# dev_kit.net
KiCad netlist of a schematic drawn in EasyEDA
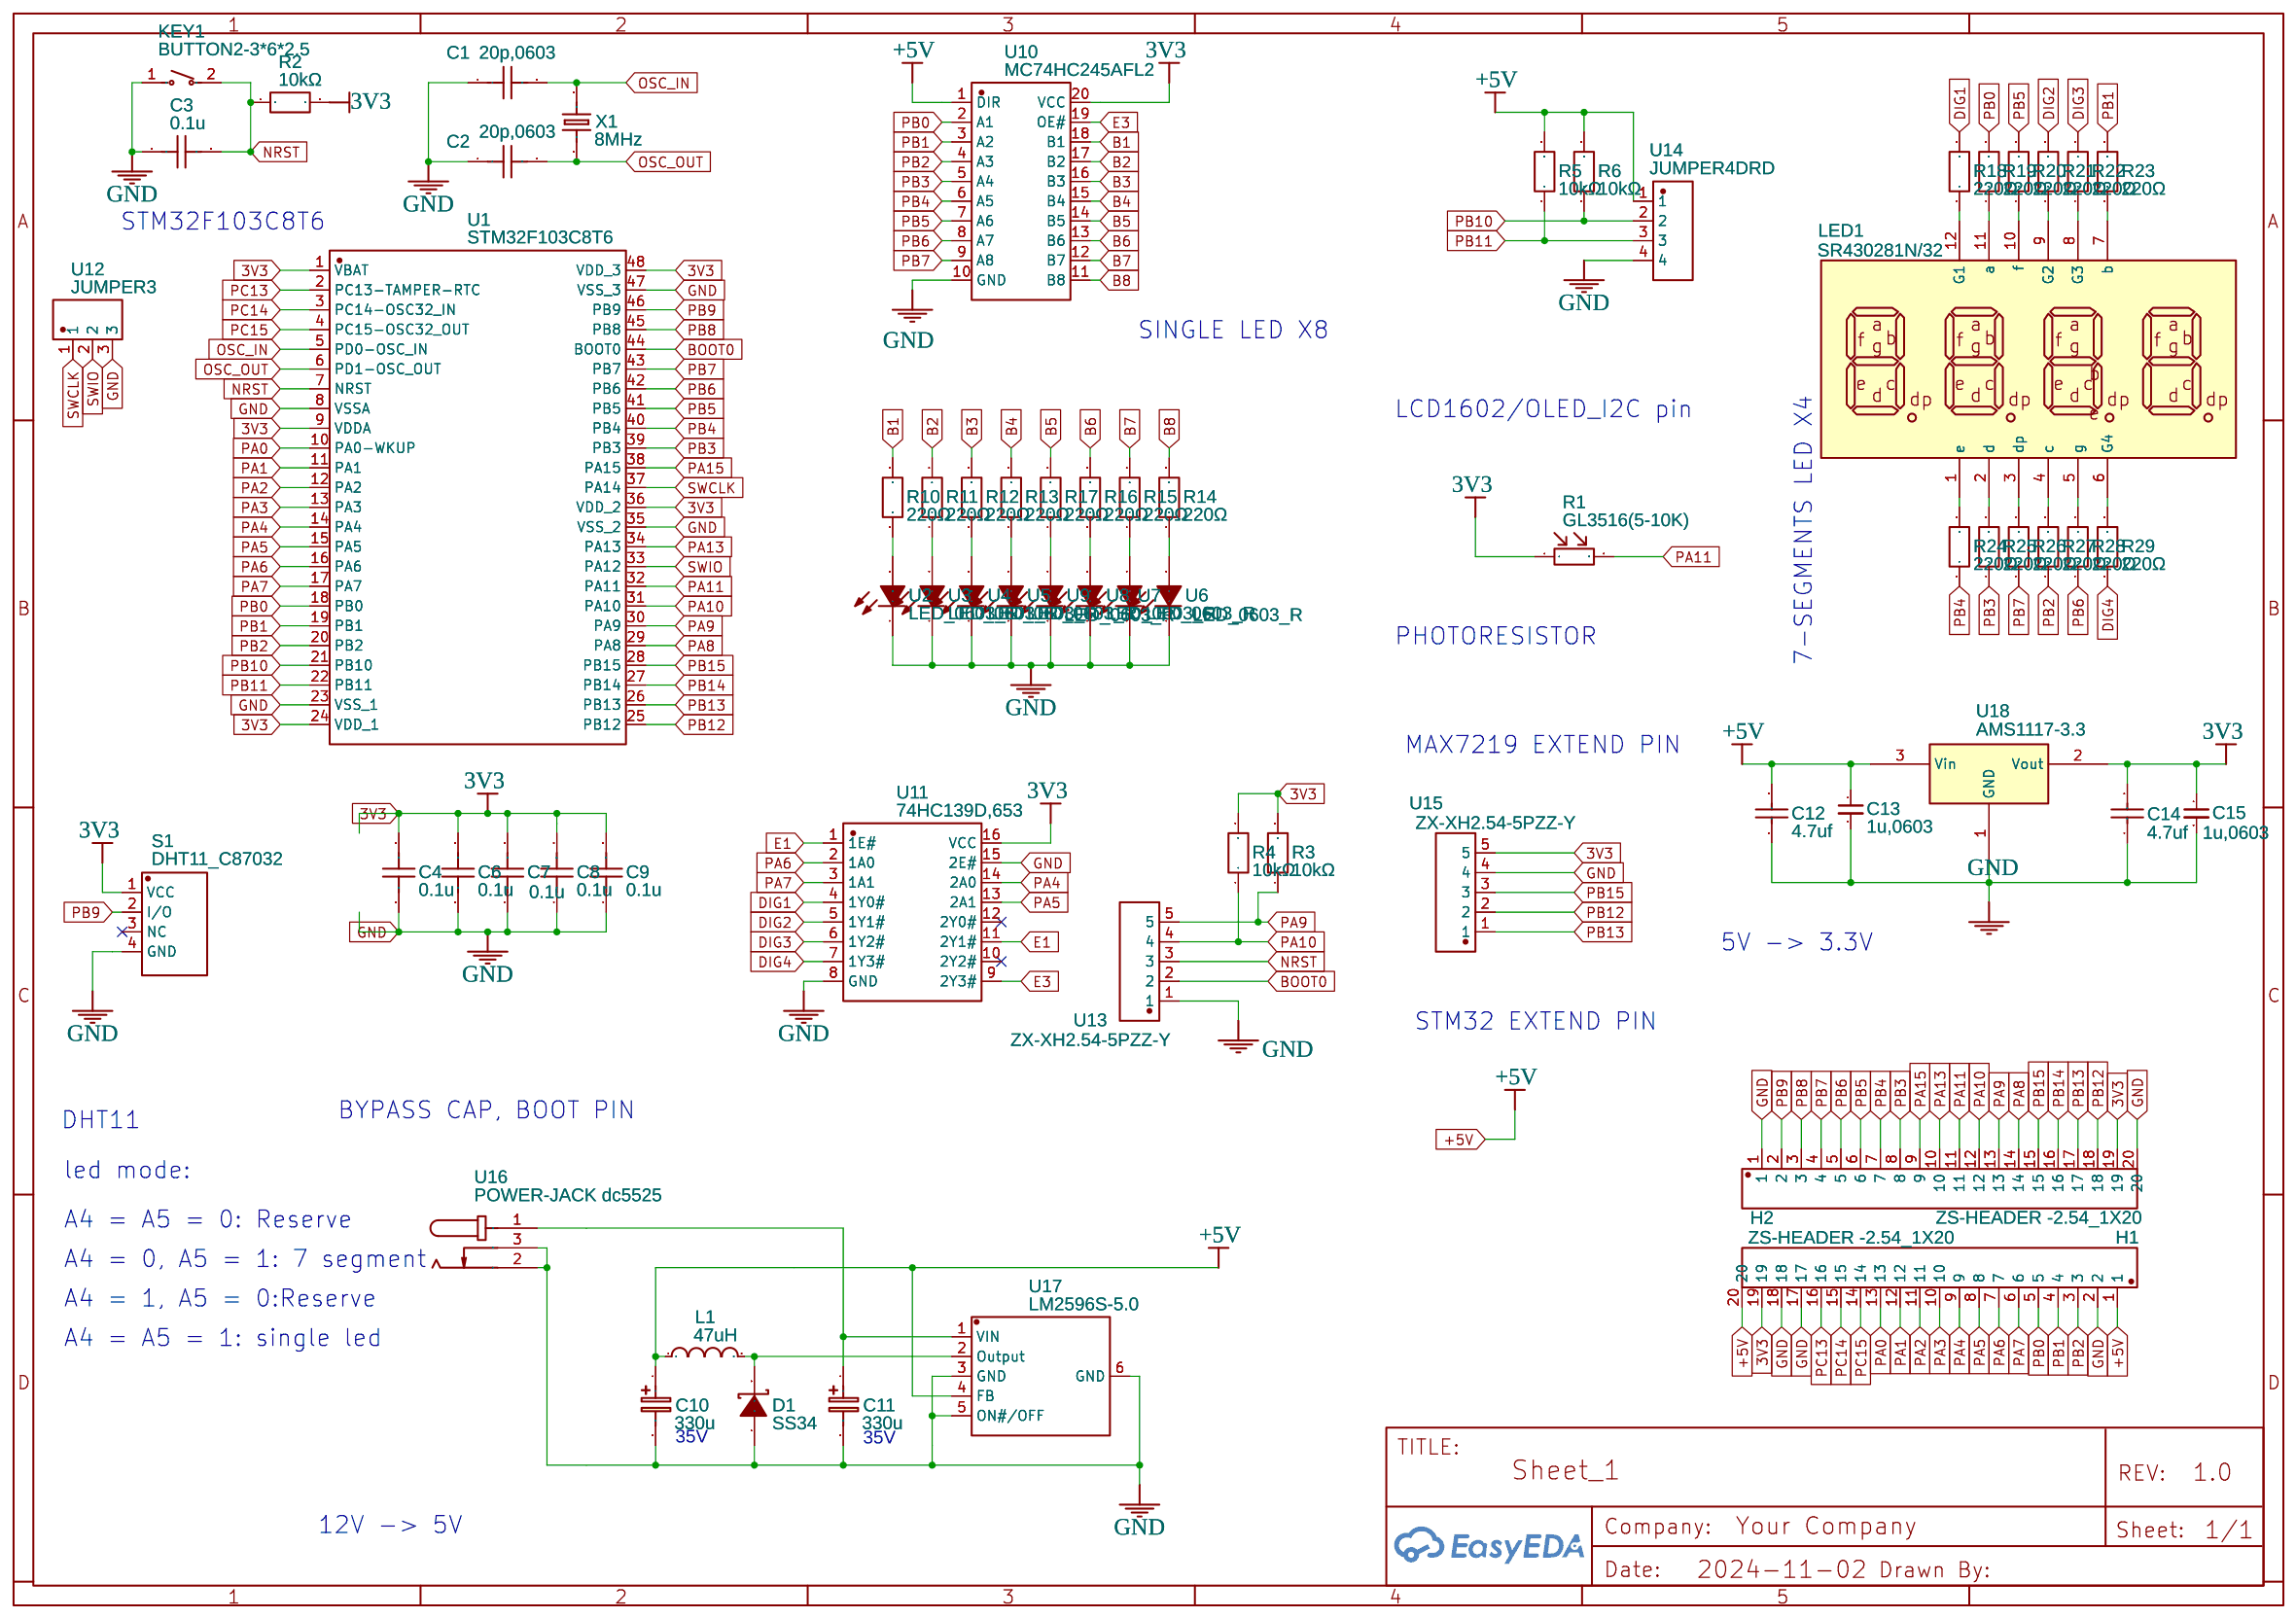
[diagram p0: schematic sheet]

(export (version "E")
  (design (tool "Eeschema 10.0.6"))
  (components
    (comp (ref "C1") (value "20p,0603") (libsource (lib "") (part "C_0603_US_1")))
    (comp (ref "C2") (value "20p,0603") (libsource (lib "") (part "C_0603_US_1")))
    (comp (ref "C3") (value "0.1u") (libsource (lib "") (part "C_0603_US_1")))
    (comp (ref "C4") (value "0.1u") (libsource (lib "") (part "C_0603_US")))
    (comp (ref "C6") (value "0.1u") (libsource (lib "") (part "C_0603_US")))
    (comp (ref "C7") (value "0.1u") (libsource (lib "") (part "C_0603_US")))
    (comp (ref "C8") (value "0.1u") (libsource (lib "") (part "C_0603_US")))
    (comp (ref "C9") (value "0.1u") (libsource (lib "") (part "C_0603_US")))
    (comp (ref "C10")
      (value "330u")
      (fields (field (name "Manufacturer Part") "?"))
      (libsource (lib "") (part "Cap_Electrolytic(SMD)_D8.0XH10.5_EU"))
    )
    (comp (ref "C11")
      (value "330u")
      (fields (field (name "Manufacturer Part") "?"))
      (libsource (lib "") (part "Cap_Electrolytic(SMD)_D8.0XH10.5_EU"))
    )
    (comp (ref "C12")
      (value "4.7uf")
      (fields (field (name "Manufacturer Part") "?"))
      (libsource (lib "") (part "Unknown_890_-400"))
    )
    (comp (ref "C13") (value "1u,0603") (libsource (lib "") (part "C_0603")))
    (comp (ref "C14")
      (value "4.7uf")
      (fields (field (name "Manufacturer Part") "?"))
      (libsource (lib "") (part "Unknown_1070_-400"))
    )
    (comp (ref "C15") (value "1u,0603") (libsource (lib "") (part "C_0603")))
    (comp (ref "D1")
      (value "SS34")
      (fields (field (name "Manufacturer") "Yenji"))
      (libsource (lib "") (part "Unknown_375_-105"))
    )
    (comp (ref "H1") (value "ZS-HEADER -2.54_1X20") (libsource (lib "") (part "ZS-HEADER -2.54_1X20_1")))
    (comp (ref "H2") (value "ZS-HEADER -2.54_1X20") (libsource (lib "") (part "ZS-HEADER -2.54_1X20")))
    (comp (ref "KEY1") (value "BUTTON2-3*6*2.5") (libsource (lib "") (part "BUTTON2-3*6*2.5")))
    (comp (ref "L1")
      (value "47uH")
      (fields (field (name "Manufacturer Part") "CDRH127NP-470MC") (field (name "Manufacturer") "Sumida"))
      (libsource (lib "") (part "CDRH127NP-470MC"))
    )
    (comp (ref "LED1")
      (value "SR430281N/32")
      (fields (field (name "Manufacturer") "ARKLED(方舟)"))
      (libsource (lib "") (part "SR430281N/32"))
    )
    (comp (ref "R1")
      (value "GL3516(5-10K)")
      (fields (field (name "Manufacturer Part") "GL3516（5-10K）") (field (name "Manufacturer") "JCHL(晶创和立)"))
      (libsource (lib "") (part "GL3516(5-10K)"))
    )
    (comp (ref "R2")
      (value "10kΩ")
      (fields (field (name "Manufacturer Part") "TD03E1002BT") (field (name "Manufacturer") "FH(风华)"))
      (libsource (lib "") (part "TD03E1002BT_1"))
    )
    (comp (ref "R3")
      (value "10kΩ")
      (fields (field (name "Manufacturer Part") "TD03E1002BT") (field (name "Manufacturer") "FH(风华)"))
      (libsource (lib "") (part "TD03E1002BT"))
    )
    (comp (ref "R4")
      (value "10kΩ")
      (fields (field (name "Manufacturer Part") "TD03E1002BT") (field (name "Manufacturer") "FH(风华)"))
      (libsource (lib "") (part "TD03E1002BT"))
    )
    (comp (ref "R5")
      (value "10kΩ")
      (fields (field (name "Manufacturer Part") "TD03E1002BT") (field (name "Manufacturer") "FH(风华)"))
      (libsource (lib "") (part "TD03E1002BT"))
    )
    (comp (ref "R6")
      (value "10kΩ")
      (fields (field (name "Manufacturer Part") "TD03E1002BT") (field (name "Manufacturer") "FH(风华)"))
      (libsource (lib "") (part "TD03E1002BT"))
    )
    (comp (ref "R10")
      (value "220Ω")
      (fields
        (field (name "Manufacturer Part") "CRCW0603220RFKEA")
        (field (name "Manufacturer") "VISHAY(威世)")
      )
      (libsource (lib "") (part "CRCW0603220RFKEA"))
    )
    (comp (ref "R11")
      (value "220Ω")
      (fields
        (field (name "Manufacturer Part") "CRCW0603220RFKEA")
        (field (name "Manufacturer") "VISHAY(威世)")
      )
      (libsource (lib "") (part "CRCW0603220RFKEA"))
    )
    (comp (ref "R12")
      (value "220Ω")
      (fields
        (field (name "Manufacturer Part") "CRCW0603220RFKEA")
        (field (name "Manufacturer") "VISHAY(威世)")
      )
      (libsource (lib "") (part "CRCW0603220RFKEA"))
    )
    (comp (ref "R13")
      (value "220Ω")
      (fields
        (field (name "Manufacturer Part") "CRCW0603220RFKEA")
        (field (name "Manufacturer") "VISHAY(威世)")
      )
      (libsource (lib "") (part "CRCW0603220RFKEA"))
    )
    (comp (ref "R14")
      (value "220Ω")
      (fields
        (field (name "Manufacturer Part") "CRCW0603220RFKEA")
        (field (name "Manufacturer") "VISHAY(威世)")
      )
      (libsource (lib "") (part "CRCW0603220RFKEA"))
    )
    (comp (ref "R15")
      (value "220Ω")
      (fields
        (field (name "Manufacturer Part") "CRCW0603220RFKEA")
        (field (name "Manufacturer") "VISHAY(威世)")
      )
      (libsource (lib "") (part "CRCW0603220RFKEA"))
    )
    (comp (ref "R16")
      (value "220Ω")
      (fields
        (field (name "Manufacturer Part") "CRCW0603220RFKEA")
        (field (name "Manufacturer") "VISHAY(威世)")
      )
      (libsource (lib "") (part "CRCW0603220RFKEA"))
    )
    (comp (ref "R17")
      (value "220Ω")
      (fields
        (field (name "Manufacturer Part") "CRCW0603220RFKEA")
        (field (name "Manufacturer") "VISHAY(威世)")
      )
      (libsource (lib "") (part "CRCW0603220RFKEA"))
    )
    (comp (ref "R18")
      (value "220Ω")
      (fields
        (field (name "Manufacturer Part") "CRCW0603220RFKEA")
        (field (name "Manufacturer") "VISHAY(威世)")
      )
      (libsource (lib "") (part "CRCW0603220RFKEA"))
    )
    (comp (ref "R19")
      (value "220Ω")
      (fields
        (field (name "Manufacturer Part") "CRCW0603220RFKEA")
        (field (name "Manufacturer") "VISHAY(威世)")
      )
      (libsource (lib "") (part "CRCW0603220RFKEA"))
    )
    (comp (ref "R20")
      (value "220Ω")
      (fields
        (field (name "Manufacturer Part") "CRCW0603220RFKEA")
        (field (name "Manufacturer") "VISHAY(威世)")
      )
      (libsource (lib "") (part "CRCW0603220RFKEA"))
    )
    (comp (ref "R21")
      (value "220Ω")
      (fields
        (field (name "Manufacturer Part") "CRCW0603220RFKEA")
        (field (name "Manufacturer") "VISHAY(威世)")
      )
      (libsource (lib "") (part "CRCW0603220RFKEA"))
    )
    (comp (ref "R22")
      (value "220Ω")
      (fields
        (field (name "Manufacturer Part") "CRCW0603220RFKEA")
        (field (name "Manufacturer") "VISHAY(威世)")
      )
      (libsource (lib "") (part "CRCW0603220RFKEA"))
    )
    (comp (ref "R23")
      (value "220Ω")
      (fields
        (field (name "Manufacturer Part") "CRCW0603220RFKEA")
        (field (name "Manufacturer") "VISHAY(威世)")
      )
      (libsource (lib "") (part "CRCW0603220RFKEA"))
    )
    (comp (ref "R24")
      (value "220Ω")
      (fields
        (field (name "Manufacturer Part") "CRCW0603220RFKEA")
        (field (name "Manufacturer") "VISHAY(威世)")
      )
      (libsource (lib "") (part "CRCW0603220RFKEA"))
    )
    (comp (ref "R25")
      (value "220Ω")
      (fields
        (field (name "Manufacturer Part") "CRCW0603220RFKEA")
        (field (name "Manufacturer") "VISHAY(威世)")
      )
      (libsource (lib "") (part "CRCW0603220RFKEA"))
    )
    (comp (ref "R26")
      (value "220Ω")
      (fields
        (field (name "Manufacturer Part") "CRCW0603220RFKEA")
        (field (name "Manufacturer") "VISHAY(威世)")
      )
      (libsource (lib "") (part "CRCW0603220RFKEA"))
    )
    (comp (ref "R27")
      (value "220Ω")
      (fields
        (field (name "Manufacturer Part") "CRCW0603220RFKEA")
        (field (name "Manufacturer") "VISHAY(威世)")
      )
      (libsource (lib "") (part "CRCW0603220RFKEA"))
    )
    (comp (ref "R28")
      (value "220Ω")
      (fields
        (field (name "Manufacturer Part") "CRCW0603220RFKEA")
        (field (name "Manufacturer") "VISHAY(威世)")
      )
      (libsource (lib "") (part "CRCW0603220RFKEA"))
    )
    (comp (ref "R29")
      (value "220Ω")
      (fields
        (field (name "Manufacturer Part") "CRCW0603220RFKEA")
        (field (name "Manufacturer") "VISHAY(威世)")
      )
      (libsource (lib "") (part "CRCW0603220RFKEA"))
    )
    (comp (ref "S1")
      (value "DHT11_C87032")
      (fields (field (name "Manufacturer Part") "DHT11") (field (name "Manufacturer") "AOSONG"))
      (libsource (lib "") (part "DHT11_C87032"))
    )
    (comp (ref "U1")
      (value "STM32F103C8T6")
      (fields (field (name "Manufacturer") "ST(意法半导体)"))
      (libsource (lib "") (part "STM32F103C8T6"))
    )
    (comp (ref "U2") (value "LED_0603_R") (libsource (lib "") (part "LED_0603_R")))
    (comp (ref "U3") (value "LED_0603_R") (libsource (lib "") (part "LED_0603_R")))
    (comp (ref "U4") (value "LED_0603_R") (libsource (lib "") (part "LED_0603_R")))
    (comp (ref "U5") (value "LED_0603_R") (libsource (lib "") (part "LED_0603_R")))
    (comp (ref "U6") (value "LED_0603_R") (libsource (lib "") (part "LED_0603_R")))
    (comp (ref "U7") (value "LED_0603_R") (libsource (lib "") (part "LED_0603_R")))
    (comp (ref "U8") (value "LED_0603_R") (libsource (lib "") (part "LED_0603_R")))
    (comp (ref "U9") (value "LED_0603_R") (libsource (lib "") (part "LED_0603_R")))
    (comp (ref "U10")
      (value "MC74HC245AFL2")
      (fields (field (name "Manufacturer") "MOTOROLA(摩托罗拉)"))
      (libsource (lib "") (part "MC74HC245AFL2"))
    )
    (comp (ref "U11")
      (value "74HC139D,653")
      (fields (field (name "Manufacturer") "Nexperia(安世)"))
      (libsource (lib "") (part "74HC139D,653"))
    )
    (comp (ref "U12")
      (value "JUMPER3")
      (fields (field (name "Manufacturer Part") "Jumper3"))
      (libsource (lib "") (part "JUMPER3"))
    )
    (comp (ref "U13")
      (value "ZX-XH2.54-5PZZ-Y")
      (fields (field (name "Manufacturer") "Megastar(兆星)"))
      (libsource (lib "") (part "ZX-XH2.54-5PZZ-Y"))
    )
    (comp (ref "U14")
      (value "JUMPER4DRD")
      (fields (field (name "Manufacturer Part") "Jumper4"))
      (libsource (lib "") (part "JUMPER4DRD"))
    )
    (comp (ref "U15")
      (value "ZX-XH2.54-5PZZ-Y")
      (fields (field (name "Manufacturer") "Megastar(兆星)"))
      (libsource (lib "") (part "ZX-XH2.54-5PZZ-Y"))
    )
    (comp (ref "U16")
      (value "POWER-JACK dc5525")
      (fields (field (name "Manufacturer Part") "POWER-JACK"))
      (libsource (lib "") (part "POWER-JACK dc5525"))
    )
    (comp (ref "U17")
      (value "LM2596S-5.0")
      (fields
        (field (name "Manufacturer Part") "LM2596S-5.0/NOPB")
        (field (name "Manufacturer") "Texas Instruments")
      )
      (libsource (lib "") (part "Unknown_520_-120"))
    )
    (comp (ref "U18")
      (value "AMS1117-3.3")
      (fields (field (name "Manufacturer Part") "?"))
      (libsource (lib "") (part "Unknown_1000_-420"))
    )
    (comp (ref "X1")
      (value "8MHz")
      (fields
        (field (name "Manufacturer Part") "49S-8.00-20-10-10/A")
        (field (name "Manufacturer") "LIMING(利明)")
      )
      (libsource (lib "") (part "49S-8.00-20-10-10/A"))
    )
  )
  (nets
    (net (code "1") (name "+5V") (class "Default")
      (node (ref "C10") (pin "1") (pinfunction "1_1") (pintype "unspecified"))
      (node (ref "C12") (pin "2") (pinfunction "2_2") (pintype "unspecified"))
      (node (ref "C13") (pin "1") (pintype "unspecified"))
      (node (ref "H2") (pin "1") (pinfunction "1_1") (pintype "unspecified"))
      (node (ref "H2") (pin "20") (pinfunction "20_20") (pintype "unspecified"))
      (node (ref "L1") (pin "1") (pinfunction "1_1") (pintype "unspecified"))
      (node (ref "R5") (pin "2") (pinfunction "2_2") (pintype "unspecified"))
      (node (ref "R6") (pin "2") (pinfunction "2_2") (pintype "unspecified"))
      (node (ref "U10") (pin "1") (pinfunction "DIR_1") (pintype "unspecified"))
      (node (ref "U14") (pin "1") (pinfunction "1_1") (pintype "unspecified"))
      (node (ref "U17") (pin "4") (pinfunction "FB_4") (pintype "unspecified"))
      (node (ref "U18") (pin "3") (pinfunction "Vin_3") (pintype "unspecified"))
    )
    (net (code "2") (name "3V3") (class "Default")
      (node (ref "C14") (pin "2") (pinfunction "2_2") (pintype "unspecified"))
      (node (ref "C15") (pin "1") (pintype "unspecified"))
      (node (ref "C4") (pin "2") (pinfunction "2_2") (pintype "unspecified"))
      (node (ref "C6") (pin "2") (pinfunction "2_2") (pintype "unspecified"))
      (node (ref "C7") (pin "2") (pinfunction "2_2") (pintype "unspecified"))
      (node (ref "C8") (pin "2") (pinfunction "2_2") (pintype "unspecified"))
      (node (ref "C9") (pin "2") (pinfunction "2_2") (pintype "unspecified"))
      (node (ref "H1") (pin "19") (pinfunction "19_19") (pintype "unspecified"))
      (node (ref "H2") (pin "19") (pinfunction "19_19") (pintype "unspecified"))
      (node (ref "R1") (pin "1") (pinfunction "1_1") (pintype "input"))
      (node (ref "R2") (pin "2") (pinfunction "2_2") (pintype "unspecified"))
      (node (ref "R3") (pin "2") (pinfunction "2_2") (pintype "unspecified"))
      (node (ref "R4") (pin "2") (pinfunction "2_2") (pintype "unspecified"))
      (node (ref "S1") (pin "1") (pinfunction "VCC_1") (pintype "unspecified"))
      (node (ref "U1") (pin "1") (pinfunction "VBAT_1") (pintype "unspecified"))
      (node (ref "U1") (pin "24") (pinfunction "VDD_1_24") (pintype "unspecified"))
      (node (ref "U1") (pin "36") (pinfunction "VDD_2_36") (pintype "unspecified"))
      (node (ref "U1") (pin "48") (pinfunction "VDD_3_48") (pintype "unspecified"))
      (node (ref "U1") (pin "9") (pinfunction "VDDA_9") (pintype "unspecified"))
      (node (ref "U10") (pin "20") (pinfunction "VCC_20") (pintype "unspecified"))
      (node (ref "U11") (pin "16") (pinfunction "VCC_16") (pintype "unspecified"))
      (node (ref "U15") (pin "5") (pinfunction "5_5") (pintype "unspecified"))
      (node (ref "U18") (pin "2") (pinfunction "Vout_2") (pintype "unspecified"))
    )
    (net (code "3") (name "B1") (class "Default")
      (node (ref "R10") (pin "2") (pinfunction "2_2") (pintype "unspecified"))
      (node (ref "U10") (pin "18") (pinfunction "B1_18") (pintype "unspecified"))
    )
    (net (code "4") (name "B2") (class "Default")
      (node (ref "R11") (pin "2") (pinfunction "2_2") (pintype "unspecified"))
      (node (ref "U10") (pin "17") (pinfunction "B2_17") (pintype "unspecified"))
    )
    (net (code "5") (name "B3") (class "Default")
      (node (ref "R12") (pin "2") (pinfunction "2_2") (pintype "unspecified"))
      (node (ref "U10") (pin "16") (pinfunction "B3_16") (pintype "unspecified"))
    )
    (net (code "6") (name "B4") (class "Default")
      (node (ref "R13") (pin "2") (pinfunction "2_2") (pintype "unspecified"))
      (node (ref "U10") (pin "15") (pinfunction "B4_15") (pintype "unspecified"))
    )
    (net (code "7") (name "B5") (class "Default")
      (node (ref "R17") (pin "2") (pinfunction "2_2") (pintype "unspecified"))
      (node (ref "U10") (pin "14") (pinfunction "B5_14") (pintype "unspecified"))
    )
    (net (code "8") (name "B6") (class "Default")
      (node (ref "R16") (pin "2") (pinfunction "2_2") (pintype "unspecified"))
      (node (ref "U10") (pin "13") (pinfunction "B6_13") (pintype "unspecified"))
    )
    (net (code "9") (name "B7") (class "Default")
      (node (ref "R15") (pin "2") (pinfunction "2_2") (pintype "unspecified"))
      (node (ref "U10") (pin "12") (pinfunction "B7_12") (pintype "unspecified"))
    )
    (net (code "10") (name "B8") (class "Default")
      (node (ref "R14") (pin "2") (pinfunction "2_2") (pintype "unspecified"))
      (node (ref "U10") (pin "11") (pinfunction "B8_11") (pintype "unspecified"))
    )
    (net (code "11") (name "BOOT0") (class "Default")
      (node (ref "U1") (pin "44") (pinfunction "BOOT0_44") (pintype "unspecified"))
      (node (ref "U13") (pin "2") (pinfunction "2_2") (pintype "unspecified"))
    )
    (net (code "12") (name "DIG1") (class "Default")
      (node (ref "R18") (pin "2") (pinfunction "2_2") (pintype "unspecified"))
      (node (ref "U11") (pin "4") (pinfunction "1Y0#_4") (pintype "unspecified"))
    )
    (net (code "13") (name "DIG2") (class "Default")
      (node (ref "R21") (pin "2") (pinfunction "2_2") (pintype "unspecified"))
      (node (ref "U11") (pin "5") (pinfunction "1Y1#_5") (pintype "unspecified"))
    )
    (net (code "14") (name "DIG3") (class "Default")
      (node (ref "R22") (pin "2") (pinfunction "2_2") (pintype "unspecified"))
      (node (ref "U11") (pin "6") (pinfunction "1Y2#_6") (pintype "unspecified"))
    )
    (net (code "15") (name "DIG4") (class "Default")
      (node (ref "R29") (pin "1") (pinfunction "1_1") (pintype "unspecified"))
      (node (ref "U11") (pin "7") (pinfunction "1Y3#_7") (pintype "unspecified"))
    )
    (net (code "16") (name "E1") (class "Default")
      (node (ref "U11") (pin "1") (pinfunction "1E#_1") (pintype "unspecified"))
      (node (ref "U11") (pin "11") (pinfunction "2Y1#_11") (pintype "unspecified"))
    )
    (net (code "17") (name "E3") (class "Default")
      (node (ref "U10") (pin "19") (pinfunction "OE#_19") (pintype "unspecified"))
      (node (ref "U11") (pin "9") (pinfunction "2Y3#_9") (pintype "unspecified"))
    )
    (net (code "18") (name "GND") (class "Default")
      (node (ref "C1") (pin "1") (pinfunction "1_1") (pintype "unspecified"))
      (node (ref "C10") (pin "2") (pinfunction "2_2") (pintype "unspecified"))
      (node (ref "C11") (pin "2") (pinfunction "2_2") (pintype "unspecified"))
      (node (ref "C12") (pin "1") (pinfunction "1_1") (pintype "unspecified"))
      (node (ref "C13") (pin "2") (pintype "unspecified"))
      (node (ref "C14") (pin "1") (pinfunction "1_1") (pintype "unspecified"))
      (node (ref "C15") (pin "2") (pintype "unspecified"))
      (node (ref "C2") (pin "1") (pinfunction "1_1") (pintype "unspecified"))
      (node (ref "C3") (pin "1") (pinfunction "1_1") (pintype "unspecified"))
      (node (ref "C4") (pin "1") (pinfunction "1_1") (pintype "unspecified"))
      (node (ref "C6") (pin "1") (pinfunction "1_1") (pintype "unspecified"))
      (node (ref "C7") (pin "1") (pinfunction "1_1") (pintype "unspecified"))
      (node (ref "C8") (pin "1") (pinfunction "1_1") (pintype "unspecified"))
      (node (ref "C9") (pin "1") (pinfunction "1_1") (pintype "unspecified"))
      (node (ref "D1") (pin "1") (pinfunction "A_1") (pintype "unspecified"))
      (node (ref "H1") (pin "1") (pinfunction "1_1") (pintype "unspecified"))
      (node (ref "H1") (pin "20") (pinfunction "20_20") (pintype "unspecified"))
      (node (ref "H2") (pin "17") (pinfunction "17_17") (pintype "unspecified"))
      (node (ref "H2") (pin "18") (pinfunction "18_18") (pintype "unspecified"))
      (node (ref "H2") (pin "2") (pinfunction "2_2") (pintype "unspecified"))
      (node (ref "KEY1") (pin "1") (pinfunction "1_1") (pintype "unspecified"))
      (node (ref "S1") (pin "4") (pinfunction "GND_4") (pintype "unspecified"))
      (node (ref "U1") (pin "23") (pinfunction "VSS_1_23") (pintype "unspecified"))
      (node (ref "U1") (pin "35") (pinfunction "VSS_2_35") (pintype "unspecified"))
      (node (ref "U1") (pin "47") (pinfunction "VSS_3_47") (pintype "unspecified"))
      (node (ref "U1") (pin "8") (pinfunction "VSSA_8") (pintype "unspecified"))
      (node (ref "U10") (pin "10") (pinfunction "GND_10") (pintype "unspecified"))
      (node (ref "U11") (pin "15") (pinfunction "2E#_15") (pintype "unspecified"))
      (node (ref "U11") (pin "8") (pinfunction "GND_8") (pintype "unspecified"))
      (node (ref "U12") (pin "3") (pinfunction "3_3") (pintype "unspecified"))
      (node (ref "U13") (pin "1") (pinfunction "1_1") (pintype "unspecified"))
      (node (ref "U14") (pin "4") (pinfunction "4_4") (pintype "unspecified"))
      (node (ref "U15") (pin "4") (pinfunction "4_4") (pintype "unspecified"))
      (node (ref "U16") (pin "2") (pinfunction "2_2") (pintype "unspecified"))
      (node (ref "U16") (pin "3") (pinfunction "3_3") (pintype "unspecified"))
      (node (ref "U17") (pin "3") (pinfunction "GND_3") (pintype "unspecified"))
      (node (ref "U17") (pin "5") (pinfunction "ON#/OFF_5") (pintype "unspecified"))
      (node (ref "U17") (pin "6") (pinfunction "GND_6") (pintype "unspecified"))
      (node (ref "U18") (pin "1") (pinfunction "GND_1") (pintype "unspecified"))
      (node (ref "U2") (pin "1") (pinfunction "-_1") (pintype "input"))
      (node (ref "U3") (pin "1") (pinfunction "-_1") (pintype "input"))
      (node (ref "U4") (pin "1") (pinfunction "-_1") (pintype "input"))
      (node (ref "U5") (pin "1") (pinfunction "-_1") (pintype "input"))
      (node (ref "U6") (pin "1") (pinfunction "-_1") (pintype "input"))
      (node (ref "U7") (pin "1") (pinfunction "-_1") (pintype "input"))
      (node (ref "U8") (pin "1") (pinfunction "-_1") (pintype "input"))
      (node (ref "U9") (pin "1") (pinfunction "-_1") (pintype "input"))
    )
    (net (code "19") (name "NRST") (class "Default")
      (node (ref "C3") (pin "2") (pinfunction "2_2") (pintype "unspecified"))
      (node (ref "KEY1") (pin "2") (pinfunction "2_2") (pintype "unspecified"))
      (node (ref "R2") (pin "1") (pinfunction "1_1") (pintype "unspecified"))
      (node (ref "U1") (pin "7") (pinfunction "NRST_7") (pintype "unspecified"))
      (node (ref "U13") (pin "3") (pinfunction "3_3") (pintype "unspecified"))
    )
    (net (code "20") (name "Net-(D1-K)") (class "Default")
      (node (ref "D1") (pin "2") (pinfunction "K_2") (pintype "unspecified"))
      (node (ref "L1") (pin "2") (pinfunction "2_2") (pintype "unspecified"))
      (node (ref "U17") (pin "2") (pinfunction "Output_2") (pintype "unspecified"))
    )
    (net (code "21") (name "Net-(LED1-G1)") (class "Default")
      (node (ref "LED1") (pin "12") (pinfunction "G1_12") (pintype "input"))
      (node (ref "R18") (pin "1") (pinfunction "1_1") (pintype "unspecified"))
    )
    (net (code "22") (name "Net-(LED1-G2)") (class "Default")
      (node (ref "LED1") (pin "9") (pinfunction "G2_9") (pintype "input"))
      (node (ref "R21") (pin "1") (pinfunction "1_1") (pintype "unspecified"))
    )
    (net (code "23") (name "Net-(LED1-G3)") (class "Default")
      (node (ref "LED1") (pin "8") (pinfunction "G3_8") (pintype "input"))
      (node (ref "R22") (pin "1") (pinfunction "1_1") (pintype "unspecified"))
    )
    (net (code "24") (name "Net-(LED1-G4)") (class "Default")
      (node (ref "LED1") (pin "6") (pinfunction "G4_6") (pintype "input"))
      (node (ref "R29") (pin "2") (pinfunction "2_2") (pintype "unspecified"))
    )
    (net (code "25") (name "Net-(LED1-a)") (class "Default")
      (node (ref "LED1") (pin "11") (pinfunction "a_11") (pintype "input"))
      (node (ref "R19") (pin "1") (pinfunction "1_1") (pintype "unspecified"))
    )
    (net (code "26") (name "Net-(LED1-b)") (class "Default")
      (node (ref "LED1") (pin "7") (pinfunction "b_7") (pintype "input"))
      (node (ref "R23") (pin "1") (pinfunction "1_1") (pintype "unspecified"))
    )
    (net (code "27") (name "Net-(LED1-c)") (class "Default")
      (node (ref "LED1") (pin "4") (pinfunction "c_4") (pintype "input"))
      (node (ref "R27") (pin "2") (pinfunction "2_2") (pintype "unspecified"))
    )
    (net (code "28") (name "Net-(LED1-d)") (class "Default")
      (node (ref "LED1") (pin "2") (pinfunction "d_2") (pintype "input"))
      (node (ref "R25") (pin "2") (pinfunction "2_2") (pintype "unspecified"))
    )
    (net (code "29") (name "Net-(LED1-dp)") (class "Default")
      (node (ref "LED1") (pin "3") (pinfunction "dp_3") (pintype "input"))
      (node (ref "R26") (pin "2") (pinfunction "2_2") (pintype "unspecified"))
    )
    (net (code "30") (name "Net-(LED1-e)") (class "Default")
      (node (ref "LED1") (pin "1") (pinfunction "e_1") (pintype "input"))
      (node (ref "R24") (pin "2") (pinfunction "2_2") (pintype "unspecified"))
    )
    (net (code "31") (name "Net-(LED1-f)") (class "Default")
      (node (ref "LED1") (pin "10") (pinfunction "f_10") (pintype "input"))
      (node (ref "R20") (pin "1") (pinfunction "1_1") (pintype "unspecified"))
    )
    (net (code "32") (name "Net-(LED1-g)") (class "Default")
      (node (ref "LED1") (pin "5") (pinfunction "g_5") (pintype "input"))
      (node (ref "R28") (pin "2") (pinfunction "2_2") (pintype "unspecified"))
    )
    (net (code "33") (name "Net-(U2-+)") (class "Default")
      (node (ref "R10") (pin "1") (pinfunction "1_1") (pintype "unspecified"))
      (node (ref "U2") (pin "2") (pinfunction "+_2") (pintype "input"))
    )
    (net (code "34") (name "Net-(U3-+)") (class "Default")
      (node (ref "R11") (pin "1") (pinfunction "1_1") (pintype "unspecified"))
      (node (ref "U3") (pin "2") (pinfunction "+_2") (pintype "input"))
    )
    (net (code "35") (name "Net-(U4-+)") (class "Default")
      (node (ref "R12") (pin "1") (pinfunction "1_1") (pintype "unspecified"))
      (node (ref "U4") (pin "2") (pinfunction "+_2") (pintype "input"))
    )
    (net (code "36") (name "Net-(U5-+)") (class "Default")
      (node (ref "R13") (pin "1") (pinfunction "1_1") (pintype "unspecified"))
      (node (ref "U5") (pin "2") (pinfunction "+_2") (pintype "input"))
    )
    (net (code "37") (name "Net-(U6-+)") (class "Default")
      (node (ref "R14") (pin "1") (pinfunction "1_1") (pintype "unspecified"))
      (node (ref "U6") (pin "2") (pinfunction "+_2") (pintype "input"))
    )
    (net (code "38") (name "Net-(U7-+)") (class "Default")
      (node (ref "R15") (pin "1") (pinfunction "1_1") (pintype "unspecified"))
      (node (ref "U7") (pin "2") (pinfunction "+_2") (pintype "input"))
    )
    (net (code "39") (name "Net-(U8-+)") (class "Default")
      (node (ref "R16") (pin "1") (pinfunction "1_1") (pintype "unspecified"))
      (node (ref "U8") (pin "2") (pinfunction "+_2") (pintype "input"))
    )
    (net (code "40") (name "Net-(U9-+)") (class "Default")
      (node (ref "R17") (pin "1") (pinfunction "1_1") (pintype "unspecified"))
      (node (ref "U9") (pin "2") (pinfunction "+_2") (pintype "input"))
    )
    (net (code "41") (name "Net-(U17-VIN)") (class "Default")
      (node (ref "C11") (pin "1") (pinfunction "1_1") (pintype "unspecified"))
      (node (ref "U16") (pin "1") (pinfunction "1_1") (pintype "unspecified"))
      (node (ref "U17") (pin "1") (pinfunction "VIN_1") (pintype "unspecified"))
    )
    (net (code "42") (name "OSC_IN") (class "Default")
      (node (ref "C1") (pin "2") (pinfunction "2_2") (pintype "unspecified"))
      (node (ref "U1") (pin "5") (pinfunction "PD0-OSC_IN_5") (pintype "unspecified"))
      (node (ref "X1") (pin "2") (pinfunction "2_2") (pintype "unspecified"))
    )
    (net (code "43") (name "OSC_OUT") (class "Default")
      (node (ref "C2") (pin "2") (pinfunction "2_2") (pintype "unspecified"))
      (node (ref "U1") (pin "6") (pinfunction "PD1-OSC_OUT_6") (pintype "unspecified"))
      (node (ref "X1") (pin "1") (pinfunction "1_1") (pintype "unspecified"))
    )
    (net (code "44") (name "PA0") (class "Default")
      (node (ref "H2") (pin "13") (pinfunction "13_13") (pintype "unspecified"))
      (node (ref "U1") (pin "10") (pinfunction "PA0-WKUP_10") (pintype "unspecified"))
    )
    (net (code "45") (name "PA1") (class "Default")
      (node (ref "H2") (pin "12") (pinfunction "12_12") (pintype "unspecified"))
      (node (ref "U1") (pin "11") (pinfunction "PA1_11") (pintype "unspecified"))
    )
    (net (code "46") (name "PA2") (class "Default")
      (node (ref "H2") (pin "11") (pinfunction "11_11") (pintype "unspecified"))
      (node (ref "U1") (pin "12") (pinfunction "PA2_12") (pintype "unspecified"))
    )
    (net (code "47") (name "PA3") (class "Default")
      (node (ref "H2") (pin "10") (pinfunction "10_10") (pintype "unspecified"))
      (node (ref "U1") (pin "13") (pinfunction "PA3_13") (pintype "unspecified"))
    )
    (net (code "48") (name "PA4") (class "Default")
      (node (ref "H2") (pin "9") (pinfunction "9_9") (pintype "unspecified"))
      (node (ref "U1") (pin "14") (pinfunction "PA4_14") (pintype "unspecified"))
      (node (ref "U11") (pin "14") (pinfunction "2A0_14") (pintype "unspecified"))
    )
    (net (code "49") (name "PA5") (class "Default")
      (node (ref "H2") (pin "8") (pinfunction "8_8") (pintype "unspecified"))
      (node (ref "U1") (pin "15") (pinfunction "PA5_15") (pintype "unspecified"))
      (node (ref "U11") (pin "13") (pinfunction "2A1_13") (pintype "unspecified"))
    )
    (net (code "50") (name "PA6") (class "Default")
      (node (ref "H2") (pin "7") (pinfunction "7_7") (pintype "unspecified"))
      (node (ref "U1") (pin "16") (pinfunction "PA6_16") (pintype "unspecified"))
      (node (ref "U11") (pin "2") (pinfunction "1A0_2") (pintype "unspecified"))
    )
    (net (code "51") (name "PA7") (class "Default")
      (node (ref "H2") (pin "6") (pinfunction "6_6") (pintype "unspecified"))
      (node (ref "U1") (pin "17") (pinfunction "PA7_17") (pintype "unspecified"))
      (node (ref "U11") (pin "3") (pinfunction "1A1_3") (pintype "unspecified"))
    )
    (net (code "52") (name "PA8") (class "Default")
      (node (ref "H1") (pin "14") (pinfunction "14_14") (pintype "unspecified"))
      (node (ref "U1") (pin "29") (pinfunction "PA8_29") (pintype "unspecified"))
    )
    (net (code "53") (name "PA9") (class "Default")
      (node (ref "H1") (pin "13") (pinfunction "13_13") (pintype "unspecified"))
      (node (ref "R3") (pin "1") (pinfunction "1_1") (pintype "unspecified"))
      (node (ref "U1") (pin "30") (pinfunction "PA9_30") (pintype "unspecified"))
      (node (ref "U13") (pin "5") (pinfunction "5_5") (pintype "unspecified"))
    )
    (net (code "54") (name "PA10") (class "Default")
      (node (ref "H1") (pin "12") (pinfunction "12_12") (pintype "unspecified"))
      (node (ref "R4") (pin "1") (pinfunction "1_1") (pintype "unspecified"))
      (node (ref "U1") (pin "31") (pinfunction "PA10_31") (pintype "unspecified"))
      (node (ref "U13") (pin "4") (pinfunction "4_4") (pintype "unspecified"))
    )
    (net (code "55") (name "PA11") (class "Default")
      (node (ref "H1") (pin "11") (pinfunction "11_11") (pintype "unspecified"))
      (node (ref "R1") (pin "2") (pinfunction "2_2") (pintype "input"))
      (node (ref "U1") (pin "32") (pinfunction "PA11_32") (pintype "unspecified"))
    )
    (net (code "56") (name "PA13") (class "Default")
      (node (ref "H1") (pin "10") (pinfunction "10_10") (pintype "unspecified"))
      (node (ref "U1") (pin "34") (pinfunction "PA13_34") (pintype "unspecified"))
    )
    (net (code "57") (name "PA15") (class "Default")
      (node (ref "H1") (pin "9") (pinfunction "9_9") (pintype "unspecified"))
      (node (ref "U1") (pin "38") (pinfunction "PA15_38") (pintype "unspecified"))
    )
    (net (code "58") (name "PB0") (class "Default")
      (node (ref "H2") (pin "5") (pinfunction "5_5") (pintype "unspecified"))
      (node (ref "R19") (pin "2") (pinfunction "2_2") (pintype "unspecified"))
      (node (ref "U1") (pin "18") (pinfunction "PB0_18") (pintype "unspecified"))
      (node (ref "U10") (pin "2") (pinfunction "A1_2") (pintype "unspecified"))
    )
    (net (code "59") (name "PB1") (class "Default")
      (node (ref "H2") (pin "4") (pinfunction "4_4") (pintype "unspecified"))
      (node (ref "R23") (pin "2") (pinfunction "2_2") (pintype "unspecified"))
      (node (ref "U1") (pin "19") (pinfunction "PB1_19") (pintype "unspecified"))
      (node (ref "U10") (pin "3") (pinfunction "A2_3") (pintype "unspecified"))
    )
    (net (code "60") (name "PB2") (class "Default")
      (node (ref "H2") (pin "3") (pinfunction "3_3") (pintype "unspecified"))
      (node (ref "R27") (pin "1") (pinfunction "1_1") (pintype "unspecified"))
      (node (ref "U1") (pin "20") (pinfunction "PB2_20") (pintype "unspecified"))
      (node (ref "U10") (pin "4") (pinfunction "A3_4") (pintype "unspecified"))
    )
    (net (code "61") (name "PB3") (class "Default")
      (node (ref "H1") (pin "8") (pinfunction "8_8") (pintype "unspecified"))
      (node (ref "R25") (pin "1") (pinfunction "1_1") (pintype "unspecified"))
      (node (ref "U1") (pin "39") (pinfunction "PB3_39") (pintype "unspecified"))
      (node (ref "U10") (pin "5") (pinfunction "A4_5") (pintype "unspecified"))
    )
    (net (code "62") (name "PB4") (class "Default")
      (node (ref "H1") (pin "7") (pinfunction "7_7") (pintype "unspecified"))
      (node (ref "R24") (pin "1") (pinfunction "1_1") (pintype "unspecified"))
      (node (ref "U1") (pin "40") (pinfunction "PB4_40") (pintype "unspecified"))
      (node (ref "U10") (pin "6") (pinfunction "A5_6") (pintype "unspecified"))
    )
    (net (code "63") (name "PB5") (class "Default")
      (node (ref "H1") (pin "6") (pinfunction "6_6") (pintype "unspecified"))
      (node (ref "R20") (pin "2") (pinfunction "2_2") (pintype "unspecified"))
      (node (ref "U1") (pin "41") (pinfunction "PB5_41") (pintype "unspecified"))
      (node (ref "U10") (pin "7") (pinfunction "A6_7") (pintype "unspecified"))
    )
    (net (code "64") (name "PB6") (class "Default")
      (node (ref "H1") (pin "5") (pinfunction "5_5") (pintype "unspecified"))
      (node (ref "R28") (pin "1") (pinfunction "1_1") (pintype "unspecified"))
      (node (ref "U1") (pin "42") (pinfunction "PB6_42") (pintype "unspecified"))
      (node (ref "U10") (pin "8") (pinfunction "A7_8") (pintype "unspecified"))
    )
    (net (code "65") (name "PB7") (class "Default")
      (node (ref "H1") (pin "4") (pinfunction "4_4") (pintype "unspecified"))
      (node (ref "R26") (pin "1") (pinfunction "1_1") (pintype "unspecified"))
      (node (ref "U1") (pin "43") (pinfunction "PB7_43") (pintype "unspecified"))
      (node (ref "U10") (pin "9") (pinfunction "A8_9") (pintype "unspecified"))
    )
    (net (code "66") (name "PB8") (class "Default")
      (node (ref "H1") (pin "3") (pinfunction "3_3") (pintype "unspecified"))
      (node (ref "U1") (pin "45") (pinfunction "PB8_45") (pintype "unspecified"))
    )
    (net (code "67") (name "PB9") (class "Default")
      (node (ref "H1") (pin "2") (pinfunction "2_2") (pintype "unspecified"))
      (node (ref "S1") (pin "2") (pinfunction "I/O_2") (pintype "unspecified"))
      (node (ref "U1") (pin "46") (pinfunction "PB9_46") (pintype "unspecified"))
    )
    (net (code "68") (name "PB10") (class "Default")
      (node (ref "R6") (pin "1") (pinfunction "1_1") (pintype "unspecified"))
      (node (ref "U1") (pin "21") (pinfunction "PB10_21") (pintype "unspecified"))
      (node (ref "U14") (pin "2") (pinfunction "2_2") (pintype "unspecified"))
    )
    (net (code "69") (name "PB11") (class "Default")
      (node (ref "R5") (pin "1") (pinfunction "1_1") (pintype "unspecified"))
      (node (ref "U1") (pin "22") (pinfunction "PB11_22") (pintype "unspecified"))
      (node (ref "U14") (pin "3") (pinfunction "3_3") (pintype "unspecified"))
    )
    (net (code "70") (name "PB12") (class "Default")
      (node (ref "H1") (pin "18") (pinfunction "18_18") (pintype "unspecified"))
      (node (ref "U1") (pin "25") (pinfunction "PB12_25") (pintype "unspecified"))
      (node (ref "U15") (pin "2") (pinfunction "2_2") (pintype "unspecified"))
    )
    (net (code "71") (name "PB13") (class "Default")
      (node (ref "H1") (pin "17") (pinfunction "17_17") (pintype "unspecified"))
      (node (ref "U1") (pin "26") (pinfunction "PB13_26") (pintype "unspecified"))
      (node (ref "U15") (pin "1") (pinfunction "1_1") (pintype "unspecified"))
    )
    (net (code "72") (name "PB14") (class "Default")
      (node (ref "H1") (pin "16") (pinfunction "16_16") (pintype "unspecified"))
      (node (ref "U1") (pin "27") (pinfunction "PB14_27") (pintype "unspecified"))
    )
    (net (code "73") (name "PB15") (class "Default")
      (node (ref "H1") (pin "15") (pinfunction "15_15") (pintype "unspecified"))
      (node (ref "U1") (pin "28") (pinfunction "PB15_28") (pintype "unspecified"))
      (node (ref "U15") (pin "3") (pinfunction "3_3") (pintype "unspecified"))
    )
    (net (code "74") (name "PC13") (class "Default")
      (node (ref "H2") (pin "16") (pinfunction "16_16") (pintype "unspecified"))
      (node (ref "U1") (pin "2") (pinfunction "PC13-TAMPER-RTC_2") (pintype "unspecified"))
    )
    (net (code "75") (name "PC14") (class "Default")
      (node (ref "H2") (pin "15") (pinfunction "15_15") (pintype "unspecified"))
      (node (ref "U1") (pin "3") (pinfunction "PC14-OSC32_IN_3") (pintype "unspecified"))
    )
    (net (code "76") (name "PC15") (class "Default")
      (node (ref "H2") (pin "14") (pinfunction "14_14") (pintype "unspecified"))
      (node (ref "U1") (pin "4") (pinfunction "PC15-OSC32_OUT_4") (pintype "unspecified"))
    )
    (net (code "77") (name "SWCLK") (class "Default")
      (node (ref "U1") (pin "37") (pinfunction "PA14_37") (pintype "unspecified"))
      (node (ref "U12") (pin "1") (pinfunction "1_1") (pintype "unspecified"))
    )
    (net (code "78") (name "SWIO") (class "Default")
      (node (ref "U1") (pin "33") (pinfunction "PA12_33") (pintype "unspecified"))
      (node (ref "U12") (pin "2") (pinfunction "2_2") (pintype "unspecified"))
    )
    (net (code "79") (name "unconnected-(S1-NC-Pad3)") (class "Default")
      (node (ref "S1") (pin "3") (pinfunction "NC_3") (pintype "unspecified+no_connect"))
    )
    (net (code "80") (name "unconnected-(U11-2Y0#-Pad12)") (class "Default")
      (node (ref "U11") (pin "12") (pinfunction "2Y0#_12") (pintype "unspecified+no_connect"))
    )
    (net (code "81") (name "unconnected-(U11-2Y2#-Pad10)") (class "Default")
      (node (ref "U11") (pin "10") (pinfunction "2Y2#_10") (pintype "unspecified+no_connect"))
    )
  )
)
